# RGB_Matrix.net
KiCad netlist of a schematic drawn in Altium Designer
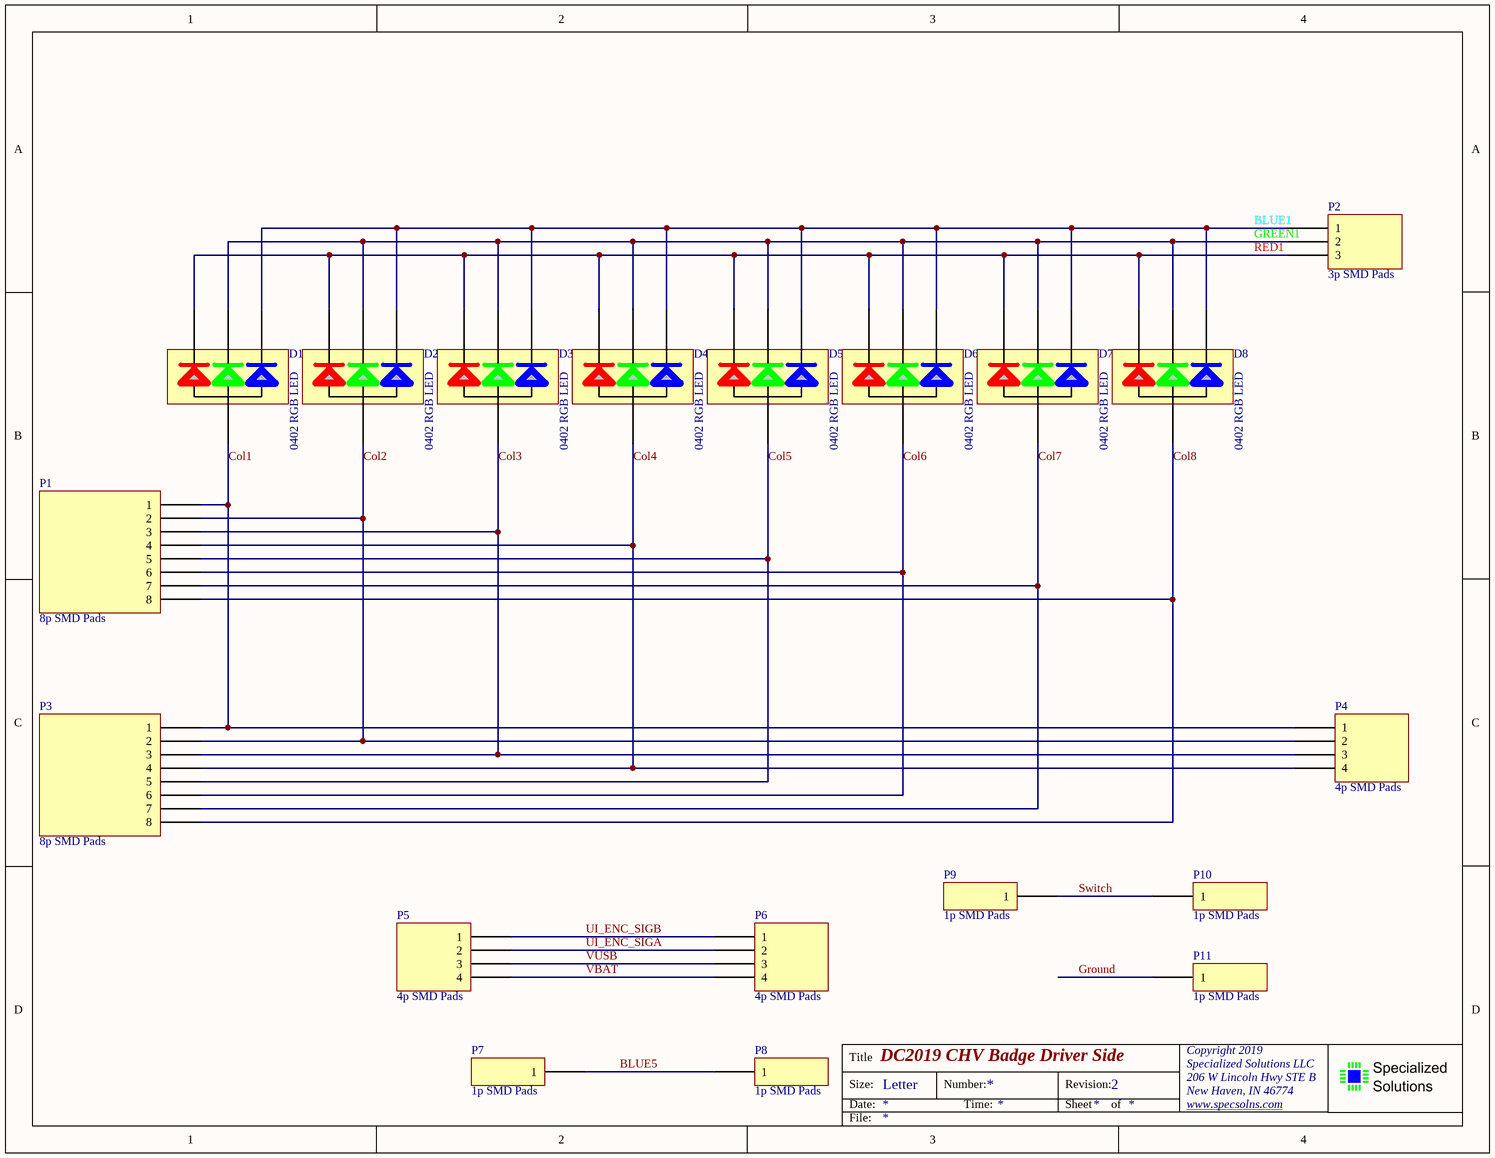
[diagram p0: RGB Matrix.SchDoc]

(export (version "E")
  (design (tool "Eeschema 10.0.6"))
  (components
    (comp (ref "D1")
      (value "0402 RGB LED")
      (footprint "0404 RGB LED")
      (libsource (lib "Parts") (part "0402 RGB LED"))
    )
    (comp (ref "D2")
      (value "0402 RGB LED")
      (footprint "0404 RGB LED")
      (libsource (lib "Parts") (part "0402 RGB LED"))
    )
    (comp (ref "D3")
      (value "0402 RGB LED")
      (footprint "0404 RGB LED")
      (libsource (lib "Parts") (part "0402 RGB LED"))
    )
    (comp (ref "D4")
      (value "0402 RGB LED")
      (footprint "0404 RGB LED")
      (libsource (lib "Parts") (part "0402 RGB LED"))
    )
    (comp (ref "D5")
      (value "0402 RGB LED")
      (footprint "0404 RGB LED")
      (libsource (lib "Parts") (part "0402 RGB LED"))
    )
    (comp (ref "D6")
      (value "0402 RGB LED")
      (footprint "0404 RGB LED")
      (libsource (lib "Parts") (part "0402 RGB LED"))
    )
    (comp (ref "D7")
      (value "0402 RGB LED")
      (footprint "0404 RGB LED")
      (libsource (lib "Parts") (part "0402 RGB LED"))
    )
    (comp (ref "D8")
      (value "0402 RGB LED")
      (footprint "0404 RGB LED")
      (libsource (lib "Parts") (part "0402 RGB LED"))
    )
    (comp (ref "P1")
      (value "8p SMD Pads")
      (footprint "8p SMD pad")
      (libsource (lib "parts") (part "8p SMD Pads"))
    )
    (comp (ref "P2")
      (value "3p SMD Pads")
      (footprint "3p SMD pad")
      (libsource (lib "parts (carol's conflicted copy 2019-04-30)") (part "3p SMD"))
    )
    (comp (ref "P3")
      (value "8p SMD Pads")
      (footprint "8p SMD pad")
      (libsource (lib "parts") (part "8p SMD Pads"))
    )
    (comp (ref "P4") (value "4p SMD Pads") (footprint "4p SMD pad") (libsource (lib "parts") (part "4p SMD")))
    (comp (ref "P5") (value "4p SMD Pads") (footprint "4p SMD pad") (libsource (lib "") (part "4p SMD_1")))
    (comp (ref "P6") (value "4p SMD Pads") (footprint "4p SMD pad") (libsource (lib "parts") (part "4p SMD")))
    (comp (ref "P7") (value "1p SMD Pads") (footprint "1p SMD pad") (libsource (lib "") (part "1p SMD_1")))
    (comp (ref "P8") (value "1p SMD Pads") (footprint "1p SMD pad") (libsource (lib "parts") (part "1p SMD")))
    (comp (ref "P9") (value "1p SMD Pads") (footprint "1p SMD pad") (libsource (lib "") (part "1p SMD_1")))
    (comp (ref "P10")
      (value "1p SMD Pads")
      (footprint "1p SMD pad")
      (libsource (lib "parts") (part "1p SMD"))
    )
    (comp (ref "P11")
      (value "1p SMD Pads")
      (footprint "1p SMD pad")
      (libsource (lib "parts") (part "1p SMD"))
    )
  )
  (nets
    (net (code "1") (name "/BLUE1") (class "Default")
      (node (ref "D1") (pin "4") (pintype "passive"))
      (node (ref "D2") (pin "4") (pintype "passive"))
      (node (ref "D3") (pin "4") (pintype "passive"))
      (node (ref "D4") (pin "4") (pintype "passive"))
      (node (ref "D5") (pin "4") (pintype "passive"))
      (node (ref "D6") (pin "4") (pintype "passive"))
      (node (ref "D7") (pin "4") (pintype "passive"))
      (node (ref "D8") (pin "4") (pintype "passive"))
      (node (ref "P2") (pin "1") (pinfunction "1_1") (pintype "passive"))
    )
    (net (code "2") (name "/BLUE5") (class "Default")
      (node (ref "P7") (pin "1") (pinfunction "1_1") (pintype "passive"))
      (node (ref "P8") (pin "1") (pinfunction "1_1") (pintype "passive"))
    )
    (net (code "3") (name "/Col1") (class "Default")
      (node (ref "D1") (pin "1") (pintype "passive"))
      (node (ref "P1") (pin "1") (pinfunction "1_1") (pintype "passive"))
      (node (ref "P3") (pin "1") (pinfunction "1_1") (pintype "passive"))
      (node (ref "P4") (pin "1") (pinfunction "1_1") (pintype "passive"))
    )
    (net (code "4") (name "/Col2") (class "Default")
      (node (ref "D2") (pin "1") (pintype "passive"))
      (node (ref "P1") (pin "2") (pinfunction "2_2") (pintype "passive"))
      (node (ref "P3") (pin "2") (pinfunction "2_2") (pintype "passive"))
      (node (ref "P4") (pin "2") (pinfunction "2_2") (pintype "passive"))
    )
    (net (code "5") (name "/Col3") (class "Default")
      (node (ref "D3") (pin "1") (pintype "passive"))
      (node (ref "P1") (pin "3") (pinfunction "3_3") (pintype "passive"))
      (node (ref "P3") (pin "3") (pinfunction "3_3") (pintype "passive"))
      (node (ref "P4") (pin "3") (pinfunction "3_3") (pintype "passive"))
    )
    (net (code "6") (name "/Col4") (class "Default")
      (node (ref "D4") (pin "1") (pintype "passive"))
      (node (ref "P1") (pin "4") (pinfunction "4_4") (pintype "passive"))
      (node (ref "P3") (pin "4") (pinfunction "4_4") (pintype "passive"))
      (node (ref "P4") (pin "4") (pinfunction "4_4") (pintype "passive"))
    )
    (net (code "7") (name "/Col5") (class "Default")
      (node (ref "D5") (pin "1") (pintype "passive"))
      (node (ref "P1") (pin "5") (pinfunction "5_5") (pintype "passive"))
      (node (ref "P3") (pin "5") (pinfunction "5_5") (pintype "passive"))
    )
    (net (code "8") (name "/Col6") (class "Default")
      (node (ref "D6") (pin "1") (pintype "passive"))
      (node (ref "P1") (pin "6") (pinfunction "6_6") (pintype "passive"))
      (node (ref "P3") (pin "6") (pinfunction "6_6") (pintype "passive"))
    )
    (net (code "9") (name "/Col7") (class "Default")
      (node (ref "D7") (pin "1") (pintype "passive"))
      (node (ref "P1") (pin "7") (pinfunction "7_7") (pintype "passive"))
      (node (ref "P3") (pin "7") (pinfunction "7_7") (pintype "passive"))
    )
    (net (code "10") (name "/Col8") (class "Default")
      (node (ref "D8") (pin "1") (pintype "passive"))
      (node (ref "P1") (pin "8") (pinfunction "8_8") (pintype "passive"))
      (node (ref "P3") (pin "8") (pinfunction "8_8") (pintype "passive"))
    )
    (net (code "11") (name "/GREEN1") (class "Default")
      (node (ref "D1") (pin "3") (pintype "passive"))
      (node (ref "D2") (pin "3") (pintype "passive"))
      (node (ref "D3") (pin "3") (pintype "passive"))
      (node (ref "D4") (pin "3") (pintype "passive"))
      (node (ref "D5") (pin "3") (pintype "passive"))
      (node (ref "D6") (pin "3") (pintype "passive"))
      (node (ref "D7") (pin "3") (pintype "passive"))
      (node (ref "D8") (pin "3") (pintype "passive"))
      (node (ref "P2") (pin "2") (pinfunction "2_2") (pintype "passive"))
    )
    (net (code "12") (name "/Ground") (class "Default")
      (node (ref "P11") (pin "1") (pinfunction "1_1") (pintype "passive"))
    )
    (net (code "13") (name "/RED1") (class "Default")
      (node (ref "D1") (pin "2") (pintype "passive"))
      (node (ref "D2") (pin "2") (pintype "passive"))
      (node (ref "D3") (pin "2") (pintype "passive"))
      (node (ref "D4") (pin "2") (pintype "passive"))
      (node (ref "D5") (pin "2") (pintype "passive"))
      (node (ref "D6") (pin "2") (pintype "passive"))
      (node (ref "D7") (pin "2") (pintype "passive"))
      (node (ref "D8") (pin "2") (pintype "passive"))
      (node (ref "P2") (pin "3") (pinfunction "3_3") (pintype "passive"))
    )
    (net (code "14") (name "/Switch") (class "Default")
      (node (ref "P10") (pin "1") (pinfunction "1_1") (pintype "passive"))
      (node (ref "P9") (pin "1") (pinfunction "1_1") (pintype "passive"))
    )
    (net (code "15") (name "/UI_ENC_SIGA") (class "Default")
      (node (ref "P5") (pin "2") (pinfunction "2_2") (pintype "passive"))
      (node (ref "P6") (pin "2") (pinfunction "2_2") (pintype "passive"))
    )
    (net (code "16") (name "/UI_ENC_SIGB") (class "Default")
      (node (ref "P5") (pin "1") (pinfunction "1_1") (pintype "passive"))
      (node (ref "P6") (pin "1") (pinfunction "1_1") (pintype "passive"))
    )
    (net (code "17") (name "/VBAT") (class "Default")
      (node (ref "P5") (pin "4") (pinfunction "4_4") (pintype "passive"))
      (node (ref "P6") (pin "4") (pinfunction "4_4") (pintype "passive"))
    )
    (net (code "18") (name "/VUSB") (class "Default")
      (node (ref "P5") (pin "3") (pinfunction "3_3") (pintype "passive"))
      (node (ref "P6") (pin "3") (pinfunction "3_3") (pintype "passive"))
    )
  )
)
